# NanoV3_3.net
KiCad netlist of a schematic drawn in EAGLE
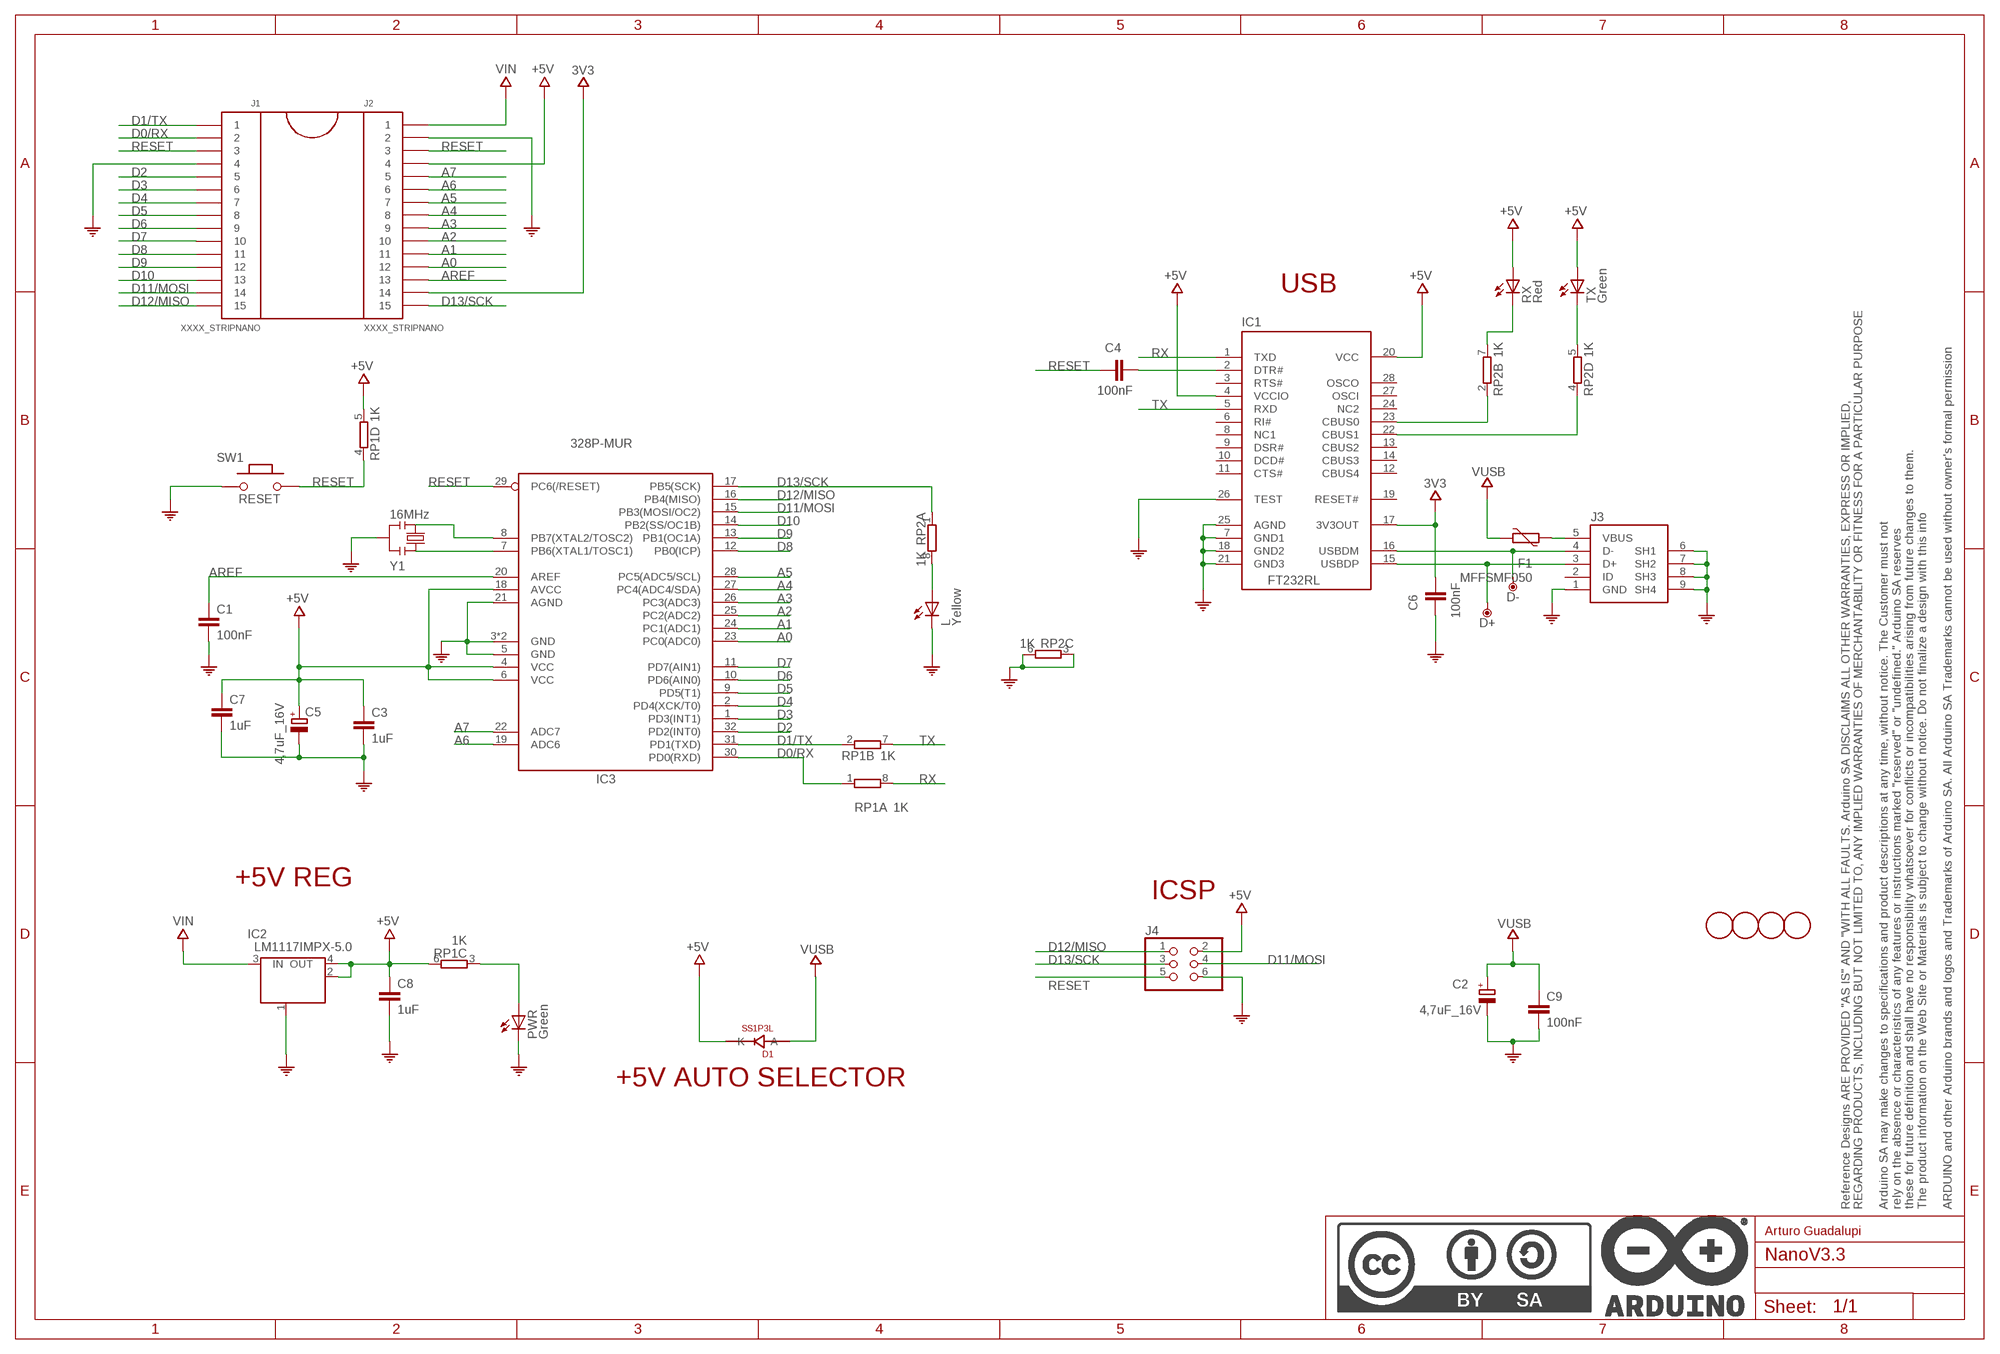
[diagram p0: schematic, sheet 1]

(export (version "E")
  (design (tool "Eeschema 10.0.6"))
  (components
    (comp (ref "C1")
      (value "100nF")
      (footprint "eagle-import:C0603-ROUND")
      (fields (field (name "PART_NUMBER") "cl10b104kbnc"))
      (libsource (lib "eagle-import") (part "0015_100NF_0603"))
    )
    (comp (ref "C2")
      (value "4,7uF_16V")
      (footprint "eagle-import:TAN-A")
      (fields (field (name "PART_NUMBER") "TAJA475MO16RNJ"))
      (libsource (lib "eagle-import") (part "0833_TAJA475MO16RNJ"))
    )
    (comp (ref "C3")
      (value "1uF")
      (footprint "eagle-import:C0603-ROUND")
      (fields (field (name "PART_NUMBER") "1uF_0603/GRM188R61E105KA12D"))
      (libsource (lib "eagle-import") (part "0006_1UF_0603/GRM188R61E105KA12D"))
    )
    (comp (ref "C4")
      (value "100nF")
      (footprint "eagle-import:C0603-ROUND")
      (fields (field (name "PART_NUMBER") "cl10b104kbnc"))
      (libsource (lib "eagle-import") (part "0015_100NF_0603"))
    )
    (comp (ref "C5")
      (value "4,7uF_16V")
      (footprint "eagle-import:TAN-A")
      (fields (field (name "PART_NUMBER") "TAJA475MO16RNJ"))
      (libsource (lib "eagle-import") (part "0833_TAJA475MO16RNJ"))
    )
    (comp (ref "C6")
      (value "100nF")
      (footprint "eagle-import:C0603-ROUND")
      (fields (field (name "PART_NUMBER") "cl10b104kbnc"))
      (libsource (lib "eagle-import") (part "0015_100NF_0603"))
    )
    (comp (ref "C7")
      (value "1uF")
      (footprint "eagle-import:C0603-ROUND")
      (fields (field (name "PART_NUMBER") "1uF_0603/GRM188R61E105KA12D"))
      (libsource (lib "eagle-import") (part "0006_1UF_0603/GRM188R61E105KA12D"))
    )
    (comp (ref "C8")
      (value "1uF")
      (footprint "eagle-import:C0603-ROUND")
      (fields (field (name "PART_NUMBER") "1uF_0603/GRM188R61E105KA12D"))
      (libsource (lib "eagle-import") (part "0006_1UF_0603/GRM188R61E105KA12D"))
    )
    (comp (ref "C9")
      (value "100nF")
      (footprint "eagle-import:C0603-ROUND")
      (fields (field (name "PART_NUMBER") "cl10b104kbnc"))
      (libsource (lib "eagle-import") (part "0015_100NF_0603"))
    )
    (comp (ref "D+")
      (value "DNP")
      (footprint "eagle-import:TP-1.00MM")
      (libsource (lib "eagle-import") (part "TPTP-1.00MM"))
    )
    (comp (ref "D-")
      (value "DNP")
      (footprint "eagle-import:TP-1.00MM")
      (libsource (lib "eagle-import") (part "TPTP-1.00MM"))
    )
    (comp (ref "D1")
      (value "SS1P3L")
      (footprint "eagle-import:DO220AAL")
      (fields (field (name "PART_NUMBER") "SS1P3L-M3/84A"))
      (libsource (lib "eagle-import") (part "0025_SS1P3L-M3/84A"))
    )
    (comp (ref "F1")
      (value "MFFSMF050")
      (footprint "eagle-import:0603-1608X90N")
      (fields (field (name "MANUFACTURER") "Bourns Inc "))
      (libsource (lib "eagle-import") (part "PTC"))
    )
    (comp (ref "FRAME1")
      (value "DNP")
      (footprint "eagle-import:FRAME")
      (libsource (lib "eagle-import") (part "A3-FRAME"))
    )
    (comp (ref "IC1")
      (value "FT232RL")
      (footprint "eagle-import:SSOP28")
      (libsource (lib "eagle-import") (part "0226_FT232RL"))
    )
    (comp (ref "IC2")
      (value "LM1117IMPX-5.0")
      (footprint "eagle-import:LINEAR_SOT223")
      (libsource (lib "eagle-import") (part "0022_LM1117IMPX-5.0"))
    )
    (comp (ref "IC3")
      (value "328P-MUR")
      (footprint "eagle-import:VQFN32")
      (fields (field (name "MANUFACTURER") "ATMEL"))
      (libsource (lib "eagle-import") (part "ATMEGA328P-32MUR"))
    )
    (comp (ref "J1")
      (value "XXXX_STRIPNANO")
      (footprint "eagle-import:HEAD15-NOSS")
      (libsource (lib "eagle-import") (part "XXXX_STRIPNANO"))
    )
    (comp (ref "J2")
      (value "XXXX_STRIPNANO")
      (footprint "eagle-import:HEAD15-NOSS")
      (libsource (lib "eagle-import") (part "XXXX_STRIPNANO"))
    )
    (comp (ref "J3")
      (value "0219_14850")
      (footprint "eagle-import:USB-MINI-B_2")
      (fields (field (name "PART_NUMBER") "14850"))
      (libsource (lib "eagle-import") (part "0219_14850"))
    )
    (comp (ref "J4")
      (value "0114_PH254-203DF118A00V")
      (footprint "eagle-import:2X03")
      (fields (field (name "PART_NUMBER") "PH254-203DF118A00V"))
      (libsource (lib "eagle-import") (part "0114_PH254-203DF118A00V"))
    )
    (comp (ref "L")
      (value "Yellow")
      (footprint "eagle-import:CHIPLED_0805")
      (fields (field (name "PART_NUMBER") "KPT-2012YC"))
      (libsource (lib "eagle-import") (part "0044_KPT-2012YC"))
    )
    (comp (ref "PWR")
      (value "Green")
      (footprint "eagle-import:CHIPLED_0805")
      (fields (field (name "PART_NUMBER") "KPT-2012SGC"))
      (libsource (lib "eagle-import") (part "0043_KPT-2012SGC"))
    )
    (comp (ref "RP1")
      (value "1K")
      (footprint "eagle-import:CAY16")
      (fields (field (name "PART_NUMBER") "064R_1K_/_CAY16-102J4LF"))
      (libsource (lib "eagle-import") (part "0005_064R_1K_/_CAY16-102J4LF"))
    )
    (comp (ref "RP2")
      (value "1K")
      (footprint "eagle-import:CAY16")
      (fields (field (name "PART_NUMBER") "064R_1K_/_CAY16-102J4LF"))
      (libsource (lib "eagle-import") (part "0005_064R_1K_/_CAY16-102J4LF"))
    )
    (comp (ref "RX")
      (value "Red")
      (footprint "eagle-import:CHIPLED_0805")
      (fields (field (name "PART_NUMBER") "KTP-2012SURCK"))
      (libsource (lib "eagle-import") (part "0181_KTP-2012SURCK"))
    )
    (comp (ref "SW1")
      (value "RESET")
      (footprint "eagle-import:SMD_157SW")
      (fields (field (name "PART_NUMBER") "IT-1185AP1C-160G-G_T&R"))
      (libsource (lib "eagle-import") (part "0173_IT-1185AP1C-160G-G_T&R"))
    )
    (comp (ref "TX")
      (value "Green")
      (footprint "eagle-import:CHIPLED_0805")
      (fields (field (name "PART_NUMBER") "KPT-2012SGC"))
      (libsource (lib "eagle-import") (part "0043_KPT-2012SGC"))
    )
    (comp (ref "U$4")
      (value "DNP")
      (footprint "eagle-import:FD-1-1.5")
      (libsource (lib "eagle-import") (part "FIDUCIAL-1.5MM"))
    )
    (comp (ref "U$5")
      (value "DNP")
      (footprint "eagle-import:FD-1-1.5")
      (libsource (lib "eagle-import") (part "FIDUCIAL-1.5MM"))
    )
    (comp (ref "U$53")
      (value "DNP")
      (footprint "eagle-import:FD-1-1.5")
      (libsource (lib "eagle-import") (part "FIDUCIAL-1.5MM"))
    )
    (comp (ref "U$54")
      (value "DNP")
      (footprint "eagle-import:FD-1-1.5")
      (libsource (lib "eagle-import") (part "FIDUCIAL-1.5MM"))
    )
    (comp (ref "Y1")
      (value "16MHz")
      (footprint "eagle-import:RESONATOR")
      (fields (field (name "PART_NUMBER") "CSTCE16M0V53-R0"))
      (libsource (lib "eagle-import") (part "0011_CSTCE16M0V53-R0"))
    )
  )
  (nets
    (net (code "1") (name "+5V") (class "Default")
      (node (ref "C3") (pin "1") (pinfunction "1_1") (pintype "passive"))
      (node (ref "C5") (pin "1") (pinfunction "+_1") (pintype "passive"))
      (node (ref "C7") (pin "1") (pinfunction "1_1") (pintype "passive"))
      (node (ref "C8") (pin "1") (pinfunction "1_1") (pintype "passive"))
      (node (ref "D1") (pin "P$1") (pinfunction "K_P$1") (pintype "bidirectional"))
      (node (ref "IC1") (pin "20") (pinfunction "VCC_20") (pintype "power_in"))
      (node (ref "IC1") (pin "4") (pinfunction "VCCIO_4") (pintype "power_in"))
      (node (ref "IC2") (pin "2") (pinfunction "OUT_2") (pintype "passive"))
      (node (ref "IC2") (pin "4") (pinfunction "OUT_4") (pintype "passive"))
      (node (ref "IC3") (pin "18") (pinfunction "AVCC_18") (pintype "bidirectional"))
      (node (ref "IC3") (pin "4") (pinfunction "VCC_4") (pintype "bidirectional"))
      (node (ref "IC3") (pin "6") (pinfunction "VCC_6") (pintype "bidirectional"))
      (node (ref "J2") (pin "4") (pinfunction "4_4") (pintype "passive"))
      (node (ref "J4") (pin "2") (pinfunction "2_2") (pintype "passive"))
      (node (ref "RP1") (pin "5") (pinfunction "2_5") (pintype "passive"))
      (node (ref "RP1") (pin "6") (pinfunction "2_6") (pintype "passive"))
      (node (ref "RX") (pin "A") (pinfunction "A_A") (pintype "passive"))
      (node (ref "TX") (pin "A") (pinfunction "A_A") (pintype "passive"))
    )
    (net (code "2") (name "/A0") (class "Default")
      (node (ref "IC3") (pin "23") (pinfunction "PC0(ADC0)_23") (pintype "bidirectional"))
      (node (ref "J2") (pin "12") (pinfunction "12_12") (pintype "passive"))
    )
    (net (code "3") (name "/A1") (class "Default")
      (node (ref "IC3") (pin "24") (pinfunction "PC1(ADC1)_24") (pintype "bidirectional"))
      (node (ref "J2") (pin "11") (pinfunction "11_11") (pintype "passive"))
    )
    (net (code "4") (name "/A2") (class "Default")
      (node (ref "IC3") (pin "25") (pinfunction "PC2(ADC2)_25") (pintype "bidirectional"))
      (node (ref "J2") (pin "10") (pinfunction "10_10") (pintype "passive"))
    )
    (net (code "5") (name "/A3") (class "Default")
      (node (ref "IC3") (pin "26") (pinfunction "PC3(ADC3)_26") (pintype "bidirectional"))
      (node (ref "J2") (pin "9") (pinfunction "9_9") (pintype "passive"))
    )
    (net (code "6") (name "/A4") (class "Default")
      (node (ref "IC3") (pin "27") (pinfunction "PC4(ADC4/SDA)_27") (pintype "bidirectional"))
      (node (ref "J2") (pin "8") (pinfunction "8_8") (pintype "passive"))
    )
    (net (code "7") (name "/A5") (class "Default")
      (node (ref "IC3") (pin "28") (pinfunction "PC5(ADC5/SCL)_28") (pintype "bidirectional"))
      (node (ref "J2") (pin "7") (pinfunction "7_7") (pintype "passive"))
    )
    (net (code "8") (name "/A6") (class "Default")
      (node (ref "IC3") (pin "19") (pinfunction "ADC6_19") (pintype "bidirectional"))
      (node (ref "J2") (pin "6") (pinfunction "6_6") (pintype "passive"))
    )
    (net (code "9") (name "/A7") (class "Default")
      (node (ref "IC3") (pin "22") (pinfunction "ADC7_22") (pintype "bidirectional"))
      (node (ref "J2") (pin "5") (pinfunction "5_5") (pintype "passive"))
    )
    (net (code "10") (name "/AREF") (class "Default")
      (node (ref "C1") (pin "1") (pinfunction "1_1") (pintype "passive"))
      (node (ref "IC3") (pin "20") (pinfunction "AREF_20") (pintype "bidirectional"))
      (node (ref "J2") (pin "13") (pinfunction "13_13") (pintype "passive"))
    )
    (net (code "11") (name "/D0{slash}RX") (class "Default")
      (node (ref "IC3") (pin "30") (pinfunction "PD0(RXD)_30") (pintype "bidirectional"))
      (node (ref "J1") (pin "2") (pinfunction "2_2") (pintype "passive"))
      (node (ref "RP1") (pin "1") (pinfunction "1_1") (pintype "passive"))
    )
    (net (code "12") (name "/D1{slash}TX") (class "Default")
      (node (ref "IC3") (pin "31") (pinfunction "PD1(TXD)_31") (pintype "bidirectional"))
      (node (ref "J1") (pin "1") (pinfunction "1_1") (pintype "passive"))
      (node (ref "RP1") (pin "2") (pinfunction "1_2") (pintype "passive"))
    )
    (net (code "13") (name "/D2") (class "Default")
      (node (ref "IC3") (pin "32") (pinfunction "PD2(INT0)_32") (pintype "bidirectional"))
      (node (ref "J1") (pin "5") (pinfunction "5_5") (pintype "passive"))
    )
    (net (code "14") (name "/D3") (class "Default")
      (node (ref "IC3") (pin "1") (pinfunction "PD3(INT1)_1") (pintype "bidirectional"))
      (node (ref "J1") (pin "6") (pinfunction "6_6") (pintype "passive"))
    )
    (net (code "15") (name "/D4") (class "Default")
      (node (ref "IC3") (pin "2") (pinfunction "PD4(XCK/T0)_2") (pintype "bidirectional"))
      (node (ref "J1") (pin "7") (pinfunction "7_7") (pintype "passive"))
    )
    (net (code "16") (name "/D5") (class "Default")
      (node (ref "IC3") (pin "9") (pinfunction "PD5(T1)_9") (pintype "bidirectional"))
      (node (ref "J1") (pin "8") (pinfunction "8_8") (pintype "passive"))
    )
    (net (code "17") (name "/D6") (class "Default")
      (node (ref "IC3") (pin "10") (pinfunction "PD6(AIN0)_10") (pintype "bidirectional"))
      (node (ref "J1") (pin "9") (pinfunction "9_9") (pintype "passive"))
    )
    (net (code "18") (name "/D7") (class "Default")
      (node (ref "IC3") (pin "11") (pinfunction "PD7(AIN1)_11") (pintype "bidirectional"))
      (node (ref "J1") (pin "10") (pinfunction "10_10") (pintype "passive"))
    )
    (net (code "19") (name "/D8") (class "Default")
      (node (ref "IC3") (pin "12") (pinfunction "PB0(ICP)_12") (pintype "bidirectional"))
      (node (ref "J1") (pin "11") (pinfunction "11_11") (pintype "passive"))
    )
    (net (code "20") (name "/D9") (class "Default")
      (node (ref "IC3") (pin "13") (pinfunction "PB1(OC1A)_13") (pintype "bidirectional"))
      (node (ref "J1") (pin "12") (pinfunction "12_12") (pintype "passive"))
    )
    (net (code "21") (name "/D10") (class "Default")
      (node (ref "IC3") (pin "14") (pinfunction "PB2(SS/OC1B)_14") (pintype "bidirectional"))
      (node (ref "J1") (pin "13") (pinfunction "13_13") (pintype "passive"))
    )
    (net (code "22") (name "/D11{slash}MOSI") (class "Default")
      (node (ref "IC3") (pin "15") (pinfunction "PB3(MOSI/OC2)_15") (pintype "bidirectional"))
      (node (ref "J1") (pin "14") (pinfunction "14_14") (pintype "passive"))
      (node (ref "J4") (pin "4") (pinfunction "4_4") (pintype "passive"))
    )
    (net (code "23") (name "/D12{slash}MISO") (class "Default")
      (node (ref "IC3") (pin "16") (pinfunction "PB4(MISO)_16") (pintype "bidirectional"))
      (node (ref "J1") (pin "15") (pinfunction "15_15") (pintype "passive"))
      (node (ref "J4") (pin "1") (pinfunction "1_1") (pintype "passive"))
    )
    (net (code "24") (name "/D13{slash}SCK") (class "Default")
      (node (ref "IC3") (pin "17") (pinfunction "PB5(SCK)_17") (pintype "bidirectional"))
      (node (ref "J2") (pin "15") (pinfunction "15_15") (pintype "passive"))
      (node (ref "J4") (pin "3") (pinfunction "3_3") (pintype "passive"))
      (node (ref "RP2") (pin "1") (pinfunction "1_1") (pintype "passive"))
    )
    (net (code "25") (name "/RESET") (class "Default")
      (node (ref "C4") (pin "1") (pinfunction "1_1") (pintype "passive"))
      (node (ref "IC3") (pin "29") (pinfunction "PC6(/RESET)_29") (pintype "bidirectional"))
      (node (ref "J1") (pin "3") (pinfunction "3_3") (pintype "passive"))
      (node (ref "J2") (pin "3") (pinfunction "3_3") (pintype "passive"))
      (node (ref "J4") (pin "5") (pinfunction "5_5") (pintype "passive"))
      (node (ref "RP1") (pin "4") (pinfunction "1_4") (pintype "passive"))
      (node (ref "SW1") (pin "2") (pinfunction "2_2") (pintype "passive"))
    )
    (net (code "26") (name "/RX") (class "Default")
      (node (ref "IC1") (pin "1") (pinfunction "TXD_1") (pintype "output"))
      (node (ref "RP1") (pin "8") (pinfunction "2_8") (pintype "passive"))
    )
    (net (code "27") (name "/TX") (class "Default")
      (node (ref "IC1") (pin "5") (pinfunction "RXD_5") (pintype "input"))
      (node (ref "RP1") (pin "7") (pinfunction "2_7") (pintype "passive"))
    )
    (net (code "28") (name "3V3") (class "Default")
      (node (ref "C6") (pin "2") (pinfunction "2_2") (pintype "passive"))
      (node (ref "IC1") (pin "17") (pinfunction "3V3OUT_17") (pintype "power_in"))
      (node (ref "J2") (pin "14") (pinfunction "14_14") (pintype "passive"))
    )
    (net (code "29") (name "COM") (class "Default")
      (node (ref "C1") (pin "2") (pinfunction "2_2") (pintype "passive"))
      (node (ref "C2") (pin "2") (pinfunction "-_2") (pintype "passive"))
      (node (ref "C3") (pin "2") (pinfunction "2_2") (pintype "passive"))
      (node (ref "C5") (pin "2") (pinfunction "-_2") (pintype "passive"))
      (node (ref "C6") (pin "1") (pinfunction "1_1") (pintype "passive"))
      (node (ref "C7") (pin "2") (pinfunction "2_2") (pintype "passive"))
      (node (ref "C8") (pin "2") (pinfunction "2_2") (pintype "passive"))
      (node (ref "C9") (pin "2") (pinfunction "2_2") (pintype "passive"))
      (node (ref "IC1") (pin "18") (pinfunction "GND2_18") (pintype "power_in"))
      (node (ref "IC1") (pin "21") (pinfunction "GND3_21") (pintype "power_in"))
      (node (ref "IC1") (pin "25") (pinfunction "AGND_25") (pintype "power_in"))
      (node (ref "IC1") (pin "26") (pinfunction "TEST_26") (pintype "bidirectional"))
      (node (ref "IC1") (pin "7") (pinfunction "GND1_7") (pintype "power_in"))
      (node (ref "IC2") (pin "1") (pinfunction "GND/ADJ_1") (pintype "input"))
      (node (ref "IC3") (pin "21") (pinfunction "AGND_21") (pintype "bidirectional"))
      (node (ref "IC3") (pin "3") (pinfunction "GND_3") (pintype "bidirectional"))
      (node (ref "IC3") (pin "33") (pinfunction "GND_33") (pintype "bidirectional"))
      (node (ref "IC3") (pin "5") (pinfunction "GND_5") (pintype "bidirectional"))
      (node (ref "J1") (pin "4") (pinfunction "4_4") (pintype "passive"))
      (node (ref "J2") (pin "2") (pinfunction "2_2") (pintype "passive"))
      (node (ref "J3") (pin "1") (pinfunction "GND_1") (pintype "passive"))
      (node (ref "J3") (pin "6") (pinfunction "SH1_6") (pintype "passive"))
      (node (ref "J3") (pin "7") (pinfunction "SH2_7") (pintype "passive"))
      (node (ref "J3") (pin "8") (pinfunction "SH3_8") (pintype "passive"))
      (node (ref "J3") (pin "9") (pinfunction "SH4_9") (pintype "passive"))
      (node (ref "J4") (pin "6") (pinfunction "6_6") (pintype "passive"))
      (node (ref "L") (pin "C") (pinfunction "C_C") (pintype "passive"))
      (node (ref "PWR") (pin "C") (pinfunction "C_C") (pintype "passive"))
      (node (ref "RP2") (pin "3") (pinfunction "1_3") (pintype "passive"))
      (node (ref "RP2") (pin "6") (pinfunction "2_6") (pintype "passive"))
      (node (ref "SW1") (pin "1") (pinfunction "1_1") (pintype "passive"))
      (node (ref "Y1") (pin "2") (pinfunction "2_2") (pintype "passive"))
    )
    (net (code "30") (name "Net-(D+-P$1)") (class "Default")
      (node (ref "D+") (pin "X") (pinfunction "P$1_X") (pintype "passive"))
      (node (ref "IC1") (pin "15") (pinfunction "USBDP_15") (pintype "bidirectional"))
      (node (ref "J3") (pin "3") (pinfunction "D+_3") (pintype "bidirectional"))
    )
    (net (code "31") (name "Net-(D--P$1)") (class "Default")
      (node (ref "D-") (pin "X") (pinfunction "P$1_X") (pintype "passive"))
      (node (ref "IC1") (pin "16") (pinfunction "USBDM_16") (pintype "bidirectional"))
      (node (ref "J3") (pin "4") (pinfunction "D-_4") (pintype "bidirectional"))
    )
    (net (code "32") (name "Net-(IC1-CBUS0)") (class "Default")
      (node (ref "IC1") (pin "23") (pinfunction "CBUS0_23") (pintype "bidirectional"))
      (node (ref "RP2") (pin "2") (pinfunction "1_2") (pintype "passive"))
    )
    (net (code "33") (name "Net-(IC1-CBUS1)") (class "Default")
      (node (ref "IC1") (pin "22") (pinfunction "CBUS1_22") (pintype "bidirectional"))
      (node (ref "RP2") (pin "4") (pinfunction "1_4") (pintype "passive"))
    )
    (net (code "34") (name "Net-(IC1-DTR#)") (class "Default")
      (node (ref "C4") (pin "2") (pinfunction "2_2") (pintype "passive"))
      (node (ref "IC1") (pin "2") (pinfunction "DTR#_2") (pintype "output"))
    )
    (net (code "35") (name "Net-(IC3-PB6(XTAL1{slash}TOSC1))") (class "Default")
      (node (ref "IC3") (pin "7") (pinfunction "PB6(XTAL1/TOSC1)_7") (pintype "bidirectional"))
      (node (ref "Y1") (pin "1") (pinfunction "1_1") (pintype "passive"))
    )
    (net (code "36") (name "Net-(IC3-PB7(XTAL2{slash}TOSC2))") (class "Default")
      (node (ref "IC3") (pin "8") (pinfunction "PB7(XTAL2/TOSC2)_8") (pintype "bidirectional"))
      (node (ref "Y1") (pin "3") (pinfunction "3_3") (pintype "passive"))
    )
    (net (code "37") (name "Net-(J3-VBUS)") (class "Default")
      (node (ref "F1") (pin "2") (pinfunction "2_2") (pintype "passive"))
      (node (ref "J3") (pin "5") (pinfunction "VBUS_5") (pintype "power_in"))
    )
    (net (code "38") (name "Net-(RP1C-1)") (class "Default")
      (node (ref "PWR") (pin "A") (pinfunction "A_A") (pintype "passive"))
      (node (ref "RP1") (pin "3") (pinfunction "1_3") (pintype "passive"))
    )
    (net (code "39") (name "Net-(RP2A-2)") (class "Default")
      (node (ref "L") (pin "A") (pinfunction "A_A") (pintype "passive"))
      (node (ref "RP2") (pin "8") (pinfunction "2_8") (pintype "passive"))
    )
    (net (code "40") (name "Net-(RP2B-2)") (class "Default")
      (node (ref "RP2") (pin "7") (pinfunction "2_7") (pintype "passive"))
      (node (ref "RX") (pin "C") (pinfunction "C_C") (pintype "passive"))
    )
    (net (code "41") (name "Net-(RP2D-2)") (class "Default")
      (node (ref "RP2") (pin "5") (pinfunction "2_5") (pintype "passive"))
      (node (ref "TX") (pin "C") (pinfunction "C_C") (pintype "passive"))
    )
    (net (code "42") (name "VIN") (class "Default")
      (node (ref "IC2") (pin "3") (pinfunction "IN_3") (pintype "input"))
      (node (ref "J2") (pin "1") (pinfunction "1_1") (pintype "passive"))
    )
    (net (code "43") (name "VUSB") (class "Default")
      (node (ref "C2") (pin "1") (pinfunction "+_1") (pintype "passive"))
      (node (ref "C9") (pin "1") (pinfunction "1_1") (pintype "passive"))
      (node (ref "D1") (pin "P$2") (pinfunction "A_P$2") (pintype "bidirectional"))
      (node (ref "F1") (pin "1") (pinfunction "1_1") (pintype "passive"))
    )
    (net (code "44") (name "unconnected-(IC1-CBUS2-Pad13)") (class "Default")
      (node (ref "IC1") (pin "13") (pinfunction "CBUS2_13") (pintype "bidirectional"))
    )
    (net (code "45") (name "unconnected-(IC1-CBUS3-Pad14)") (class "Default")
      (node (ref "IC1") (pin "14") (pinfunction "CBUS3_14") (pintype "bidirectional"))
    )
    (net (code "46") (name "unconnected-(IC1-CBUS4-Pad12)") (class "Default")
      (node (ref "IC1") (pin "12") (pinfunction "CBUS4_12") (pintype "bidirectional"))
    )
    (net (code "47") (name "unconnected-(IC1-CTS#-Pad11)") (class "Default")
      (node (ref "IC1") (pin "11") (pinfunction "CTS#_11") (pintype "bidirectional"))
    )
    (net (code "48") (name "unconnected-(IC1-DCD#-Pad10)") (class "Default")
      (node (ref "IC1") (pin "10") (pinfunction "DCD#_10") (pintype "bidirectional"))
    )
    (net (code "49") (name "unconnected-(IC1-DSR#-Pad9)") (class "Default")
      (node (ref "IC1") (pin "9") (pinfunction "DSR#_9") (pintype "bidirectional"))
    )
    (net (code "50") (name "unconnected-(IC1-NC1-Pad8)") (class "Default")
      (node (ref "IC1") (pin "8") (pinfunction "NC1_8") (pintype "bidirectional"))
    )
    (net (code "51") (name "unconnected-(IC1-NC2-Pad24)") (class "Default")
      (node (ref "IC1") (pin "24") (pinfunction "NC2_24") (pintype "no_connect"))
    )
    (net (code "52") (name "unconnected-(IC1-OSCI-Pad27)") (class "Default")
      (node (ref "IC1") (pin "27") (pinfunction "OSCI_27") (pintype "bidirectional"))
    )
    (net (code "53") (name "unconnected-(IC1-OSCO-Pad28)") (class "Default")
      (node (ref "IC1") (pin "28") (pinfunction "OSCO_28") (pintype "output"))
    )
    (net (code "54") (name "unconnected-(IC1-RESET#-Pad19)") (class "Default")
      (node (ref "IC1") (pin "19") (pinfunction "RESET#_19") (pintype "bidirectional"))
    )
    (net (code "55") (name "unconnected-(IC1-RI#-Pad6)") (class "Default")
      (node (ref "IC1") (pin "6") (pinfunction "RI#_6") (pintype "bidirectional"))
    )
    (net (code "56") (name "unconnected-(IC1-RTS#-Pad3)") (class "Default")
      (node (ref "IC1") (pin "3") (pinfunction "RTS#_3") (pintype "output"))
    )
    (net (code "57") (name "unconnected-(J3-ID-Pad2)") (class "Default")
      (node (ref "J3") (pin "2") (pinfunction "ID_2") (pintype "bidirectional"))
    )
  )
)
